# heater.net
KiCad netlist of a schematic drawn in Altium Designer
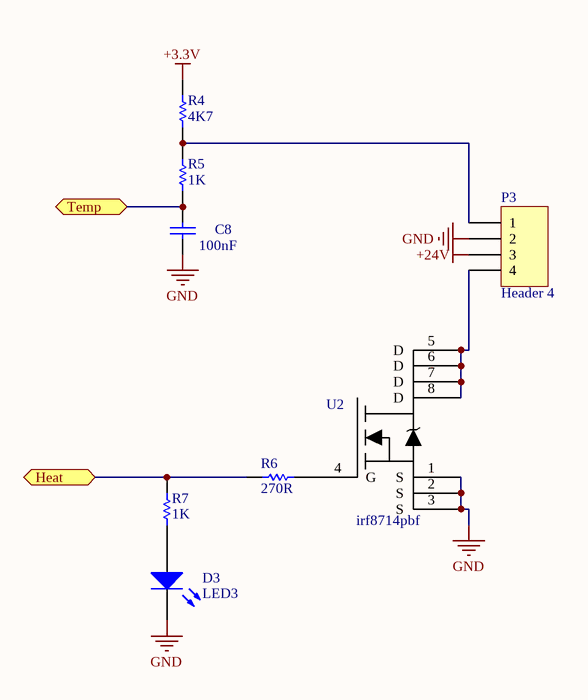
[diagram p0: heater.SchDoc]

(export (version "E")
  (design (tool "Eeschema 10.0.6"))
  (components
    (comp (ref "C8")
      (value "100nF")
      (footprint "Miscellaneous Devices:1608[0603]")
      (description "Capacitor")
      (fields (field (name "Comment") "Cap") (field (name "PUBLISHER") "Altium Limited"))
      (libsource (lib "Schematic Lib") (part "Cap"))
    )
    (comp (ref "D3")
      (value "LED3")
      (footprint "LED 0805")
      (description "Typical BLUE SiC LED")
      (fields (field (name "PUBLISHER") "Altium Limited"))
      (libsource (lib "Miscellaneous Devices") (part "LED3"))
    )
    (comp (ref "P3")
      (value "Header 4")
      (footprint "HDR1X4")
      (description "Header, 4-Pin")
      (fields (field (name "PUBLISHER") "Altium Limited"))
      (libsource (lib "Miscellaneous Connectors") (part "Header 4"))
    )
    (comp (ref "R4")
      (value "4K7")
      (footprint "J1-0603")
      (description "Resistor 0805")
      (fields (field (name "Comment") "Res") (field (name "PUBLISHER") "Altium Limited"))
      (libsource (lib "Schematic Lib") (part "Res"))
    )
    (comp (ref "R5")
      (value "1K")
      (footprint "J1-0603")
      (description "Resistor 0805")
      (fields (field (name "Comment") "Res") (field (name "PUBLISHER") "Altium Limited"))
      (libsource (lib "Schematic Lib") (part "Res"))
    )
    (comp (ref "R6")
      (value "270R")
      (footprint "J1-0603")
      (description "Resistor 0805")
      (fields (field (name "Comment") "Res") (field (name "PUBLISHER") "Altium Limited"))
      (libsource (lib "Schematic Lib") (part "Res"))
    )
    (comp (ref "R7")
      (value "1K")
      (footprint "J1-0603")
      (description "Resistor 0805")
      (fields (field (name "Comment") "Res") (field (name "PUBLISHER") "Altium Limited"))
      (libsource (lib "Schematic Lib") (part "Res"))
    )
    (comp (ref "U2")
      (value "irf8714pbf")
      (footprint "SO-8_M")
      (libsource (lib "Schlib1") (part "irf8714pbf"))
    )
  )
  (nets
    (net (code "1") (name "+3.3V") (class "Default")
      (node (ref "R4") (pin "2") (pinfunction "2_2") (pintype "passive"))
    )
    (net (code "2") (name "+24V") (class "Default")
      (node (ref "P3") (pin "3") (pinfunction "3_3") (pintype "passive"))
    )
    (net (code "3") (name "/Heat") (class "Default")
      (node (ref "R6") (pin "2") (pinfunction "2_2") (pintype "passive"))
      (node (ref "R7") (pin "2") (pinfunction "2_2") (pintype "passive"))
    )
    (net (code "4") (name "/Temp") (class "Default")
      (node (ref "C8") (pin "1") (pinfunction "1_1") (pintype "passive"))
      (node (ref "R5") (pin "1") (pinfunction "1_1") (pintype "passive"))
    )
    (net (code "5") (name "GND") (class "Default")
      (node (ref "C8") (pin "2") (pinfunction "2_2") (pintype "passive"))
      (node (ref "D3") (pin "2") (pinfunction "K_2") (pintype "passive"))
      (node (ref "P3") (pin "2") (pinfunction "2_2") (pintype "passive"))
      (node (ref "U2") (pin "1") (pinfunction "S_1") (pintype "passive"))
      (node (ref "U2") (pin "2") (pinfunction "S_2") (pintype "passive"))
      (node (ref "U2") (pin "3") (pinfunction "S_3") (pintype "passive"))
    )
    (net (code "6") (name "Net-(D3-A)") (class "Default")
      (node (ref "D3") (pin "1") (pinfunction "A_1") (pintype "passive"))
      (node (ref "R7") (pin "1") (pinfunction "1_1") (pintype "passive"))
    )
    (net (code "7") (name "Net-(P3-Pad1)") (class "Default")
      (node (ref "P3") (pin "1") (pinfunction "1_1") (pintype "passive"))
      (node (ref "R4") (pin "1") (pinfunction "1_1") (pintype "passive"))
      (node (ref "R5") (pin "2") (pinfunction "2_2") (pintype "passive"))
    )
    (net (code "8") (name "Net-(P3-Pad4)") (class "Default")
      (node (ref "P3") (pin "4") (pinfunction "4_4") (pintype "passive"))
      (node (ref "U2") (pin "5") (pinfunction "D_5") (pintype "passive"))
      (node (ref "U2") (pin "6") (pinfunction "D_6") (pintype "passive"))
      (node (ref "U2") (pin "7") (pinfunction "D_7") (pintype "passive"))
      (node (ref "U2") (pin "8") (pinfunction "D_8") (pintype "passive"))
    )
    (net (code "9") (name "Net-(U2-G)") (class "Default")
      (node (ref "R6") (pin "1") (pinfunction "1_1") (pintype "passive"))
      (node (ref "U2") (pin "4") (pinfunction "G_4") (pintype "passive"))
    )
  )
)
